# BANK32-33.net
KiCad netlist of a schematic drawn in Altium Designer
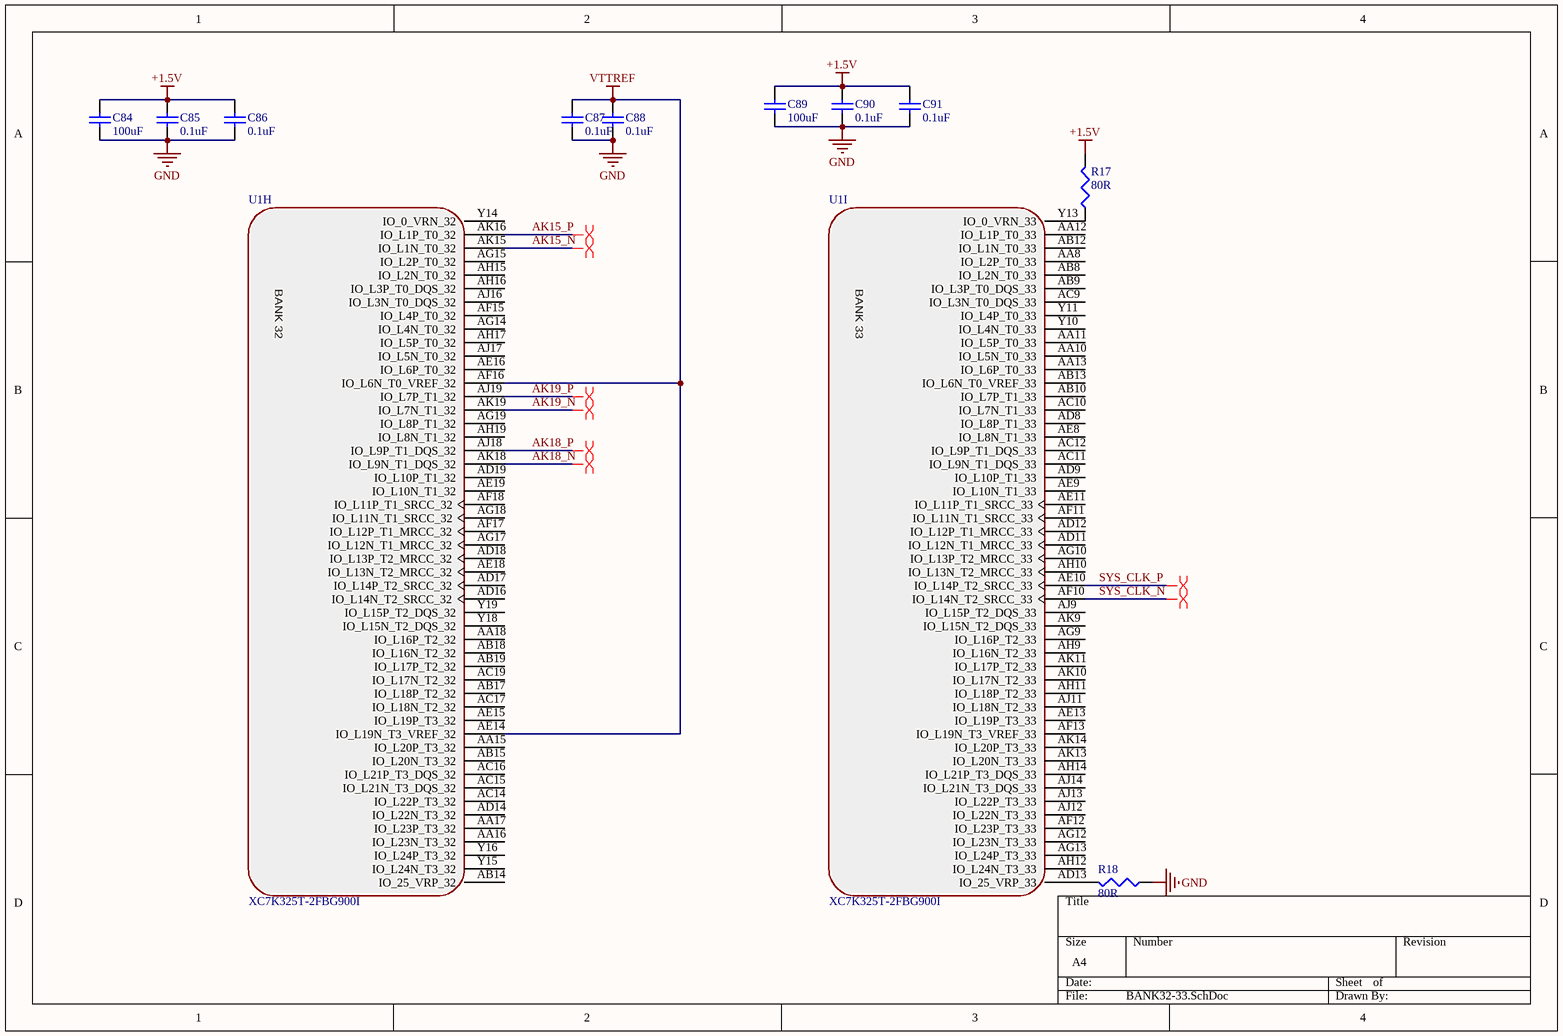
[diagram p0: BANK32-33.SchDoc]

(export (version "E")
  (design (tool "Eeschema 10.0.6"))
  (components
    (comp (ref "C84")
      (value "100uF")
      (footprint "0402")
      (description "Capacitor (Semiconductor SIM Model)")
      (fields (field (name "Comment") "Cap Semi") (field (name "PUBLISHER") "Altium Limited"))
      (libsource (lib "Miscellaneous Devices") (part "Cap Semi"))
    )
    (comp (ref "C85")
      (value "0.1uF")
      (footprint "0402")
      (description "Capacitor (Semiconductor SIM Model)")
      (fields (field (name "Comment") "Cap Semi") (field (name "PUBLISHER") "Altium Limited"))
      (libsource (lib "Miscellaneous Devices") (part "Cap Semi"))
    )
    (comp (ref "C86")
      (value "0.1uF")
      (footprint "0402")
      (description "Capacitor (Semiconductor SIM Model)")
      (fields (field (name "Comment") "Cap Semi") (field (name "PUBLISHER") "Altium Limited"))
      (libsource (lib "Miscellaneous Devices") (part "Cap Semi"))
    )
    (comp (ref "C87")
      (value "0.1uF")
      (footprint "0402")
      (description "Capacitor (Semiconductor SIM Model)")
      (fields (field (name "Comment") "Cap Semi") (field (name "PUBLISHER") "Altium Limited"))
      (libsource (lib "Miscellaneous Devices") (part "Cap Semi"))
    )
    (comp (ref "C88")
      (value "0.1uF")
      (footprint "0402")
      (description "Capacitor (Semiconductor SIM Model)")
      (fields (field (name "Comment") "Cap Semi") (field (name "PUBLISHER") "Altium Limited"))
      (libsource (lib "Miscellaneous Devices") (part "Cap Semi"))
    )
    (comp (ref "C89")
      (value "100uF")
      (footprint "0402")
      (description "Capacitor (Semiconductor SIM Model)")
      (fields (field (name "Comment") "Cap Semi") (field (name "PUBLISHER") "Altium Limited"))
      (libsource (lib "Miscellaneous Devices") (part "Cap Semi"))
    )
    (comp (ref "C90")
      (value "0.1uF")
      (footprint "0402")
      (description "Capacitor (Semiconductor SIM Model)")
      (fields (field (name "Comment") "Cap Semi") (field (name "PUBLISHER") "Altium Limited"))
      (libsource (lib "Miscellaneous Devices") (part "Cap Semi"))
    )
    (comp (ref "C91")
      (value "0.1uF")
      (footprint "0402")
      (description "Capacitor (Semiconductor SIM Model)")
      (fields (field (name "Comment") "Cap Semi") (field (name "PUBLISHER") "Altium Limited"))
      (libsource (lib "Miscellaneous Devices") (part "Cap Semi"))
    )
    (comp (ref "R17")
      (value "80R")
      (footprint "J1-0603")
      (description "Resistor")
      (fields (field (name "Comment") "Res3") (field (name "PUBLISHER") "Altium Limited"))
      (libsource (lib "Miscellaneous Devices") (part "Res3"))
    )
    (comp (ref "R18")
      (value "80R")
      (footprint "J1-0603")
      (description "Resistor")
      (fields (field (name "Comment") "Res3") (field (name "PUBLISHER") "Altium Limited"))
      (libsource (lib "Miscellaneous Devices") (part "Res3"))
    )
    (comp (ref "U1") (value "XC7K325T-2FBG900I") (libsource (lib "Schlib1") (part "XC7K325T-2FBG900I")))
  )
  (nets
    (net (code "1") (name "+1.5V") (class "Default")
      (node (ref "C84") (pin "2") (pinfunction "2_2") (pintype "passive"))
      (node (ref "C85") (pin "2") (pinfunction "2_2") (pintype "passive"))
      (node (ref "C86") (pin "2") (pinfunction "2_2") (pintype "passive"))
      (node (ref "C89") (pin "2") (pinfunction "2_2") (pintype "passive"))
      (node (ref "C90") (pin "2") (pinfunction "2_2") (pintype "passive"))
      (node (ref "C91") (pin "2") (pinfunction "2_2") (pintype "passive"))
      (node (ref "R17") (pin "2") (pinfunction "2_2") (pintype "passive"))
    )
    (net (code "2") (name "/AK15_N") (class "Default")
      (node (ref "U1") (pin "AK15") (pinfunction "IO_L1N_T0_32_AK15") (pintype "passive"))
    )
    (net (code "3") (name "/AK15_P") (class "Default")
      (node (ref "U1") (pin "AK16") (pinfunction "IO_L1P_T0_32_AK16") (pintype "passive"))
    )
    (net (code "4") (name "/AK18_N") (class "Default")
      (node (ref "U1") (pin "AK18") (pinfunction "IO_L9N_T1_DQS_32_AK18") (pintype "passive"))
    )
    (net (code "5") (name "/AK18_P") (class "Default")
      (node (ref "U1") (pin "AJ18") (pinfunction "IO_L9P_T1_DQS_32_AJ18") (pintype "passive"))
    )
    (net (code "6") (name "/AK19_N") (class "Default")
      (node (ref "U1") (pin "AK19") (pinfunction "IO_L7N_T1_32_AK19") (pintype "passive"))
    )
    (net (code "7") (name "/AK19_P") (class "Default")
      (node (ref "U1") (pin "AJ19") (pinfunction "IO_L7P_T1_32_AJ19") (pintype "passive"))
    )
    (net (code "8") (name "/SYS_CLK_N") (class "Default")
      (node (ref "U1") (pin "AF10") (pinfunction "IO_L14N_T2_SRCC_33_AF10") (pintype "passive"))
    )
    (net (code "9") (name "/SYS_CLK_P") (class "Default")
      (node (ref "U1") (pin "AE10") (pinfunction "IO_L14P_T2_SRCC_33_AE10") (pintype "passive"))
    )
    (net (code "10") (name "GND") (class "Default")
      (node (ref "C84") (pin "1") (pinfunction "1_1") (pintype "passive"))
      (node (ref "C85") (pin "1") (pinfunction "1_1") (pintype "passive"))
      (node (ref "C86") (pin "1") (pinfunction "1_1") (pintype "passive"))
      (node (ref "C87") (pin "1") (pinfunction "1_1") (pintype "passive"))
      (node (ref "C88") (pin "1") (pinfunction "1_1") (pintype "passive"))
      (node (ref "C89") (pin "1") (pinfunction "1_1") (pintype "passive"))
      (node (ref "C90") (pin "1") (pinfunction "1_1") (pintype "passive"))
      (node (ref "C91") (pin "1") (pinfunction "1_1") (pintype "passive"))
      (node (ref "R18") (pin "1") (pinfunction "1_1") (pintype "passive"))
    )
    (net (code "11") (name "Net-(U1I-IO_0_VRN_33)") (class "Default")
      (node (ref "R17") (pin "1") (pinfunction "1_1") (pintype "passive"))
      (node (ref "U1") (pin "Y13") (pinfunction "IO_0_VRN_33_Y13") (pintype "passive"))
    )
    (net (code "12") (name "Net-(U1I-IO_25_VRP_33)") (class "Default")
      (node (ref "R18") (pin "2") (pinfunction "2_2") (pintype "passive"))
      (node (ref "U1") (pin "AD13") (pinfunction "IO_25_VRP_33_AD13") (pintype "passive"))
    )
    (net (code "13") (name "VTTREF") (class "Default")
      (node (ref "C87") (pin "2") (pinfunction "2_2") (pintype "passive"))
      (node (ref "C88") (pin "2") (pinfunction "2_2") (pintype "passive"))
      (node (ref "U1") (pin "AE14") (pinfunction "IO_L19N_T3_VREF_32_AE14") (pintype "passive"))
      (node (ref "U1") (pin "AF16") (pinfunction "IO_L6N_T0_VREF_32_AF16") (pintype "passive"))
    )
    (net (code "14") (name "unconnected-(U1H-IO_0_VRN_32-PadY14)") (class "Default")
      (node (ref "U1") (pin "Y14") (pinfunction "IO_0_VRN_32_Y14") (pintype "passive"))
    )
    (net (code "15") (name "unconnected-(U1H-IO_25_VRP_32-PadAB14)") (class "Default")
      (node (ref "U1") (pin "AB14") (pinfunction "IO_25_VRP_32_AB14") (pintype "passive"))
    )
    (net (code "16") (name "unconnected-(U1H-IO_L2N_T0_32-PadAH15)") (class "Default")
      (node (ref "U1") (pin "AH15") (pinfunction "IO_L2N_T0_32_AH15") (pintype "passive"))
    )
    (net (code "17") (name "unconnected-(U1H-IO_L2P_T0_32-PadAG15)") (class "Default")
      (node (ref "U1") (pin "AG15") (pinfunction "IO_L2P_T0_32_AG15") (pintype "passive"))
    )
    (net (code "18") (name "unconnected-(U1H-IO_L3N_T0_DQS_32-PadAJ16)") (class "Default")
      (node (ref "U1") (pin "AJ16") (pinfunction "IO_L3N_T0_DQS_32_AJ16") (pintype "passive"))
    )
    (net (code "19") (name "unconnected-(U1H-IO_L3P_T0_DQS_32-PadAH16)") (class "Default")
      (node (ref "U1") (pin "AH16") (pinfunction "IO_L3P_T0_DQS_32_AH16") (pintype "passive"))
    )
    (net (code "20") (name "unconnected-(U1H-IO_L4N_T0_32-PadAG14)") (class "Default")
      (node (ref "U1") (pin "AG14") (pinfunction "IO_L4N_T0_32_AG14") (pintype "passive"))
    )
    (net (code "21") (name "unconnected-(U1H-IO_L4P_T0_32-PadAF15)") (class "Default")
      (node (ref "U1") (pin "AF15") (pinfunction "IO_L4P_T0_32_AF15") (pintype "passive"))
    )
    (net (code "22") (name "unconnected-(U1H-IO_L5N_T0_32-PadAJ17)") (class "Default")
      (node (ref "U1") (pin "AJ17") (pinfunction "IO_L5N_T0_32_AJ17") (pintype "passive"))
    )
    (net (code "23") (name "unconnected-(U1H-IO_L5P_T0_32-PadAH17)") (class "Default")
      (node (ref "U1") (pin "AH17") (pinfunction "IO_L5P_T0_32_AH17") (pintype "passive"))
    )
    (net (code "24") (name "unconnected-(U1H-IO_L6P_T0_32-PadAE16)") (class "Default")
      (node (ref "U1") (pin "AE16") (pinfunction "IO_L6P_T0_32_AE16") (pintype "passive"))
    )
    (net (code "25") (name "unconnected-(U1H-IO_L8N_T1_32-PadAH19)") (class "Default")
      (node (ref "U1") (pin "AH19") (pinfunction "IO_L8N_T1_32_AH19") (pintype "passive"))
    )
    (net (code "26") (name "unconnected-(U1H-IO_L8P_T1_32-PadAG19)") (class "Default")
      (node (ref "U1") (pin "AG19") (pinfunction "IO_L8P_T1_32_AG19") (pintype "passive"))
    )
    (net (code "27") (name "unconnected-(U1H-IO_L10N_T1_32-PadAE19)") (class "Default")
      (node (ref "U1") (pin "AE19") (pinfunction "IO_L10N_T1_32_AE19") (pintype "passive"))
    )
    (net (code "28") (name "unconnected-(U1H-IO_L10P_T1_32-PadAD19)") (class "Default")
      (node (ref "U1") (pin "AD19") (pinfunction "IO_L10P_T1_32_AD19") (pintype "passive"))
    )
    (net (code "29") (name "unconnected-(U1H-IO_L11N_T1_SRCC_32-PadAG18)") (class "Default")
      (node (ref "U1") (pin "AG18") (pinfunction "IO_L11N_T1_SRCC_32_AG18") (pintype "passive"))
    )
    (net (code "30") (name "unconnected-(U1H-IO_L11P_T1_SRCC_32-PadAF18)") (class "Default")
      (node (ref "U1") (pin "AF18") (pinfunction "IO_L11P_T1_SRCC_32_AF18") (pintype "passive"))
    )
    (net (code "31") (name "unconnected-(U1H-IO_L12N_T1_MRCC_32-PadAG17)") (class "Default")
      (node (ref "U1") (pin "AG17") (pinfunction "IO_L12N_T1_MRCC_32_AG17") (pintype "passive"))
    )
    (net (code "32") (name "unconnected-(U1H-IO_L12P_T1_MRCC_32-PadAF17)") (class "Default")
      (node (ref "U1") (pin "AF17") (pinfunction "IO_L12P_T1_MRCC_32_AF17") (pintype "passive"))
    )
    (net (code "33") (name "unconnected-(U1H-IO_L13N_T2_MRCC_32-PadAE18)") (class "Default")
      (node (ref "U1") (pin "AE18") (pinfunction "IO_L13N_T2_MRCC_32_AE18") (pintype "passive"))
    )
    (net (code "34") (name "unconnected-(U1H-IO_L13P_T2_MRCC_32-PadAD18)") (class "Default")
      (node (ref "U1") (pin "AD18") (pinfunction "IO_L13P_T2_MRCC_32_AD18") (pintype "passive"))
    )
    (net (code "35") (name "unconnected-(U1H-IO_L14N_T2_SRCC_32-PadAD16)") (class "Default")
      (node (ref "U1") (pin "AD16") (pinfunction "IO_L14N_T2_SRCC_32_AD16") (pintype "passive"))
    )
    (net (code "36") (name "unconnected-(U1H-IO_L14P_T2_SRCC_32-PadAD17)") (class "Default")
      (node (ref "U1") (pin "AD17") (pinfunction "IO_L14P_T2_SRCC_32_AD17") (pintype "passive"))
    )
    (net (code "37") (name "unconnected-(U1H-IO_L15N_T2_DQS_32-PadY18)") (class "Default")
      (node (ref "U1") (pin "Y18") (pinfunction "IO_L15N_T2_DQS_32_Y18") (pintype "passive"))
    )
    (net (code "38") (name "unconnected-(U1H-IO_L15P_T2_DQS_32-PadY19)") (class "Default")
      (node (ref "U1") (pin "Y19") (pinfunction "IO_L15P_T2_DQS_32_Y19") (pintype "passive"))
    )
    (net (code "39") (name "unconnected-(U1H-IO_L16N_T2_32-PadAB18)") (class "Default")
      (node (ref "U1") (pin "AB18") (pinfunction "IO_L16N_T2_32_AB18") (pintype "passive"))
    )
    (net (code "40") (name "unconnected-(U1H-IO_L16P_T2_32-PadAA18)") (class "Default")
      (node (ref "U1") (pin "AA18") (pinfunction "IO_L16P_T2_32_AA18") (pintype "passive"))
    )
    (net (code "41") (name "unconnected-(U1H-IO_L17N_T2_32-PadAC19)") (class "Default")
      (node (ref "U1") (pin "AC19") (pinfunction "IO_L17N_T2_32_AC19") (pintype "passive"))
    )
    (net (code "42") (name "unconnected-(U1H-IO_L17P_T2_32-PadAB19)") (class "Default")
      (node (ref "U1") (pin "AB19") (pinfunction "IO_L17P_T2_32_AB19") (pintype "passive"))
    )
    (net (code "43") (name "unconnected-(U1H-IO_L18N_T2_32-PadAC17)") (class "Default")
      (node (ref "U1") (pin "AC17") (pinfunction "IO_L18N_T2_32_AC17") (pintype "passive"))
    )
    (net (code "44") (name "unconnected-(U1H-IO_L18P_T2_32-PadAB17)") (class "Default")
      (node (ref "U1") (pin "AB17") (pinfunction "IO_L18P_T2_32_AB17") (pintype "passive"))
    )
    (net (code "45") (name "unconnected-(U1H-IO_L19P_T3_32-PadAE15)") (class "Default")
      (node (ref "U1") (pin "AE15") (pinfunction "IO_L19P_T3_32_AE15") (pintype "passive"))
    )
    (net (code "46") (name "unconnected-(U1H-IO_L20N_T3_32-PadAB15)") (class "Default")
      (node (ref "U1") (pin "AB15") (pinfunction "IO_L20N_T3_32_AB15") (pintype "passive"))
    )
    (net (code "47") (name "unconnected-(U1H-IO_L20P_T3_32-PadAA15)") (class "Default")
      (node (ref "U1") (pin "AA15") (pinfunction "IO_L20P_T3_32_AA15") (pintype "passive"))
    )
    (net (code "48") (name "unconnected-(U1H-IO_L21N_T3_DQS_32-PadAC15)") (class "Default")
      (node (ref "U1") (pin "AC15") (pinfunction "IO_L21N_T3_DQS_32_AC15") (pintype "passive"))
    )
    (net (code "49") (name "unconnected-(U1H-IO_L21P_T3_DQS_32-PadAC16)") (class "Default")
      (node (ref "U1") (pin "AC16") (pinfunction "IO_L21P_T3_DQS_32_AC16") (pintype "passive"))
    )
    (net (code "50") (name "unconnected-(U1H-IO_L22N_T3_32-PadAD14)") (class "Default")
      (node (ref "U1") (pin "AD14") (pinfunction "IO_L22N_T3_32_AD14") (pintype "passive"))
    )
    (net (code "51") (name "unconnected-(U1H-IO_L22P_T3_32-PadAC14)") (class "Default")
      (node (ref "U1") (pin "AC14") (pinfunction "IO_L22P_T3_32_AC14") (pintype "passive"))
    )
    (net (code "52") (name "unconnected-(U1H-IO_L23N_T3_32-PadAA16)") (class "Default")
      (node (ref "U1") (pin "AA16") (pinfunction "IO_L23N_T3_32_AA16") (pintype "passive"))
    )
    (net (code "53") (name "unconnected-(U1H-IO_L23P_T3_32-PadAA17)") (class "Default")
      (node (ref "U1") (pin "AA17") (pinfunction "IO_L23P_T3_32_AA17") (pintype "passive"))
    )
    (net (code "54") (name "unconnected-(U1H-IO_L24N_T3_32-PadY15)") (class "Default")
      (node (ref "U1") (pin "Y15") (pinfunction "IO_L24N_T3_32_Y15") (pintype "passive"))
    )
    (net (code "55") (name "unconnected-(U1H-IO_L24P_T3_32-PadY16)") (class "Default")
      (node (ref "U1") (pin "Y16") (pinfunction "IO_L24P_T3_32_Y16") (pintype "passive"))
    )
    (net (code "56") (name "unconnected-(U1I-IO_L1N_T0_33-PadAB12)") (class "Default")
      (node (ref "U1") (pin "AB12") (pinfunction "IO_L1N_T0_33_AB12") (pintype "passive"))
    )
    (net (code "57") (name "unconnected-(U1I-IO_L1P_T0_33-PadAA12)") (class "Default")
      (node (ref "U1") (pin "AA12") (pinfunction "IO_L1P_T0_33_AA12") (pintype "passive"))
    )
    (net (code "58") (name "unconnected-(U1I-IO_L2N_T0_33-PadAB8)") (class "Default")
      (node (ref "U1") (pin "AB8") (pinfunction "IO_L2N_T0_33_AB8") (pintype "passive"))
    )
    (net (code "59") (name "unconnected-(U1I-IO_L2P_T0_33-PadAA8)") (class "Default")
      (node (ref "U1") (pin "AA8") (pinfunction "IO_L2P_T0_33_AA8") (pintype "passive"))
    )
    (net (code "60") (name "unconnected-(U1I-IO_L3N_T0_DQS_33-PadAC9)") (class "Default")
      (node (ref "U1") (pin "AC9") (pinfunction "IO_L3N_T0_DQS_33_AC9") (pintype "passive"))
    )
    (net (code "61") (name "unconnected-(U1I-IO_L3P_T0_DQS_33-PadAB9)") (class "Default")
      (node (ref "U1") (pin "AB9") (pinfunction "IO_L3P_T0_DQS_33_AB9") (pintype "passive"))
    )
    (net (code "62") (name "unconnected-(U1I-IO_L4N_T0_33-PadY10)") (class "Default")
      (node (ref "U1") (pin "Y10") (pinfunction "IO_L4N_T0_33_Y10") (pintype "passive"))
    )
    (net (code "63") (name "unconnected-(U1I-IO_L4P_T0_33-PadY11)") (class "Default")
      (node (ref "U1") (pin "Y11") (pinfunction "IO_L4P_T0_33_Y11") (pintype "passive"))
    )
    (net (code "64") (name "unconnected-(U1I-IO_L5N_T0_33-PadAA10)") (class "Default")
      (node (ref "U1") (pin "AA10") (pinfunction "IO_L5N_T0_33_AA10") (pintype "passive"))
    )
    (net (code "65") (name "unconnected-(U1I-IO_L5P_T0_33-PadAA11)") (class "Default")
      (node (ref "U1") (pin "AA11") (pinfunction "IO_L5P_T0_33_AA11") (pintype "passive"))
    )
    (net (code "66") (name "unconnected-(U1I-IO_L6N_T0_VREF_33-PadAB13)") (class "Default")
      (node (ref "U1") (pin "AB13") (pinfunction "IO_L6N_T0_VREF_33_AB13") (pintype "passive"))
    )
    (net (code "67") (name "unconnected-(U1I-IO_L6P_T0_33-PadAA13)") (class "Default")
      (node (ref "U1") (pin "AA13") (pinfunction "IO_L6P_T0_33_AA13") (pintype "passive"))
    )
    (net (code "68") (name "unconnected-(U1I-IO_L7N_T1_33-PadAC10)") (class "Default")
      (node (ref "U1") (pin "AC10") (pinfunction "IO_L7N_T1_33_AC10") (pintype "passive"))
    )
    (net (code "69") (name "unconnected-(U1I-IO_L7P_T1_33-PadAB10)") (class "Default")
      (node (ref "U1") (pin "AB10") (pinfunction "IO_L7P_T1_33_AB10") (pintype "passive"))
    )
    (net (code "70") (name "unconnected-(U1I-IO_L8N_T1_33-PadAE8)") (class "Default")
      (node (ref "U1") (pin "AE8") (pinfunction "IO_L8N_T1_33_AE8") (pintype "passive"))
    )
    (net (code "71") (name "unconnected-(U1I-IO_L8P_T1_33-PadAD8)") (class "Default")
      (node (ref "U1") (pin "AD8") (pinfunction "IO_L8P_T1_33_AD8") (pintype "passive"))
    )
    (net (code "72") (name "unconnected-(U1I-IO_L9N_T1_DQS_33-PadAC11)") (class "Default")
      (node (ref "U1") (pin "AC11") (pinfunction "IO_L9N_T1_DQS_33_AC11") (pintype "passive"))
    )
    (net (code "73") (name "unconnected-(U1I-IO_L9P_T1_DQS_33-PadAC12)") (class "Default")
      (node (ref "U1") (pin "AC12") (pinfunction "IO_L9P_T1_DQS_33_AC12") (pintype "passive"))
    )
    (net (code "74") (name "unconnected-(U1I-IO_L10N_T1_33-PadAE9)") (class "Default")
      (node (ref "U1") (pin "AE9") (pinfunction "IO_L10N_T1_33_AE9") (pintype "passive"))
    )
    (net (code "75") (name "unconnected-(U1I-IO_L10P_T1_33-PadAD9)") (class "Default")
      (node (ref "U1") (pin "AD9") (pinfunction "IO_L10P_T1_33_AD9") (pintype "passive"))
    )
    (net (code "76") (name "unconnected-(U1I-IO_L11N_T1_SRCC_33-PadAF11)") (class "Default")
      (node (ref "U1") (pin "AF11") (pinfunction "IO_L11N_T1_SRCC_33_AF11") (pintype "passive"))
    )
    (net (code "77") (name "unconnected-(U1I-IO_L11P_T1_SRCC_33-PadAE11)") (class "Default")
      (node (ref "U1") (pin "AE11") (pinfunction "IO_L11P_T1_SRCC_33_AE11") (pintype "passive"))
    )
    (net (code "78") (name "unconnected-(U1I-IO_L12N_T1_MRCC_33-PadAD11)") (class "Default")
      (node (ref "U1") (pin "AD11") (pinfunction "IO_L12N_T1_MRCC_33_AD11") (pintype "passive"))
    )
    (net (code "79") (name "unconnected-(U1I-IO_L12P_T1_MRCC_33-PadAD12)") (class "Default")
      (node (ref "U1") (pin "AD12") (pinfunction "IO_L12P_T1_MRCC_33_AD12") (pintype "passive"))
    )
    (net (code "80") (name "unconnected-(U1I-IO_L13N_T2_MRCC_33-PadAH10)") (class "Default")
      (node (ref "U1") (pin "AH10") (pinfunction "IO_L13N_T2_MRCC_33_AH10") (pintype "passive"))
    )
    (net (code "81") (name "unconnected-(U1I-IO_L13P_T2_MRCC_33-PadAG10)") (class "Default")
      (node (ref "U1") (pin "AG10") (pinfunction "IO_L13P_T2_MRCC_33_AG10") (pintype "passive"))
    )
    (net (code "82") (name "unconnected-(U1I-IO_L15N_T2_DQS_33-PadAK9)") (class "Default")
      (node (ref "U1") (pin "AK9") (pinfunction "IO_L15N_T2_DQS_33_AK9") (pintype "passive"))
    )
    (net (code "83") (name "unconnected-(U1I-IO_L15P_T2_DQS_33-PadAJ9)") (class "Default")
      (node (ref "U1") (pin "AJ9") (pinfunction "IO_L15P_T2_DQS_33_AJ9") (pintype "passive"))
    )
    (net (code "84") (name "unconnected-(U1I-IO_L16N_T2_33-PadAH9)") (class "Default")
      (node (ref "U1") (pin "AH9") (pinfunction "IO_L16N_T2_33_AH9") (pintype "passive"))
    )
    (net (code "85") (name "unconnected-(U1I-IO_L16P_T2_33-PadAG9)") (class "Default")
      (node (ref "U1") (pin "AG9") (pinfunction "IO_L16P_T2_33_AG9") (pintype "passive"))
    )
    (net (code "86") (name "unconnected-(U1I-IO_L17N_T2_33-PadAK10)") (class "Default")
      (node (ref "U1") (pin "AK10") (pinfunction "IO_L17N_T2_33_AK10") (pintype "passive"))
    )
    (net (code "87") (name "unconnected-(U1I-IO_L17P_T2_33-PadAK11)") (class "Default")
      (node (ref "U1") (pin "AK11") (pinfunction "IO_L17P_T2_33_AK11") (pintype "passive"))
    )
    (net (code "88") (name "unconnected-(U1I-IO_L18N_T2_33-PadAJ11)") (class "Default")
      (node (ref "U1") (pin "AJ11") (pinfunction "IO_L18N_T2_33_AJ11") (pintype "passive"))
    )
    (net (code "89") (name "unconnected-(U1I-IO_L18P_T2_33-PadAH11)") (class "Default")
      (node (ref "U1") (pin "AH11") (pinfunction "IO_L18P_T2_33_AH11") (pintype "passive"))
    )
    (net (code "90") (name "unconnected-(U1I-IO_L19N_T3_VREF_33-PadAF13)") (class "Default")
      (node (ref "U1") (pin "AF13") (pinfunction "IO_L19N_T3_VREF_33_AF13") (pintype "passive"))
    )
    (net (code "91") (name "unconnected-(U1I-IO_L19P_T3_33-PadAE13)") (class "Default")
      (node (ref "U1") (pin "AE13") (pinfunction "IO_L19P_T3_33_AE13") (pintype "passive"))
    )
    (net (code "92") (name "unconnected-(U1I-IO_L20N_T3_33-PadAK13)") (class "Default")
      (node (ref "U1") (pin "AK13") (pinfunction "IO_L20N_T3_33_AK13") (pintype "passive"))
    )
    (net (code "93") (name "unconnected-(U1I-IO_L20P_T3_33-PadAK14)") (class "Default")
      (node (ref "U1") (pin "AK14") (pinfunction "IO_L20P_T3_33_AK14") (pintype "passive"))
    )
    (net (code "94") (name "unconnected-(U1I-IO_L21N_T3_DQS_33-PadAJ14)") (class "Default")
      (node (ref "U1") (pin "AJ14") (pinfunction "IO_L21N_T3_DQS_33_AJ14") (pintype "passive"))
    )
    (net (code "95") (name "unconnected-(U1I-IO_L21P_T3_DQS_33-PadAH14)") (class "Default")
      (node (ref "U1") (pin "AH14") (pinfunction "IO_L21P_T3_DQS_33_AH14") (pintype "passive"))
    )
    (net (code "96") (name "unconnected-(U1I-IO_L22N_T3_33-PadAJ12)") (class "Default")
      (node (ref "U1") (pin "AJ12") (pinfunction "IO_L22N_T3_33_AJ12") (pintype "passive"))
    )
    (net (code "97") (name "unconnected-(U1I-IO_L22P_T3_33-PadAJ13)") (class "Default")
      (node (ref "U1") (pin "AJ13") (pinfunction "IO_L22P_T3_33_AJ13") (pintype "passive"))
    )
    (net (code "98") (name "unconnected-(U1I-IO_L23N_T3_33-PadAG12)") (class "Default")
      (node (ref "U1") (pin "AG12") (pinfunction "IO_L23N_T3_33_AG12") (pintype "passive"))
    )
    (net (code "99") (name "unconnected-(U1I-IO_L23P_T3_33-PadAF12)") (class "Default")
      (node (ref "U1") (pin "AF12") (pinfunction "IO_L23P_T3_33_AF12") (pintype "passive"))
    )
    (net (code "100") (name "unconnected-(U1I-IO_L24N_T3_33-PadAH12)") (class "Default")
      (node (ref "U1") (pin "AH12") (pinfunction "IO_L24N_T3_33_AH12") (pintype "passive"))
    )
    (net (code "101") (name "unconnected-(U1I-IO_L24P_T3_33-PadAG13)") (class "Default")
      (node (ref "U1") (pin "AG13") (pinfunction "IO_L24P_T3_33_AG13") (pintype "passive"))
    )
  )
)
